# Hardwiring.net
KiCad netlist of a schematic drawn in Altium Designer
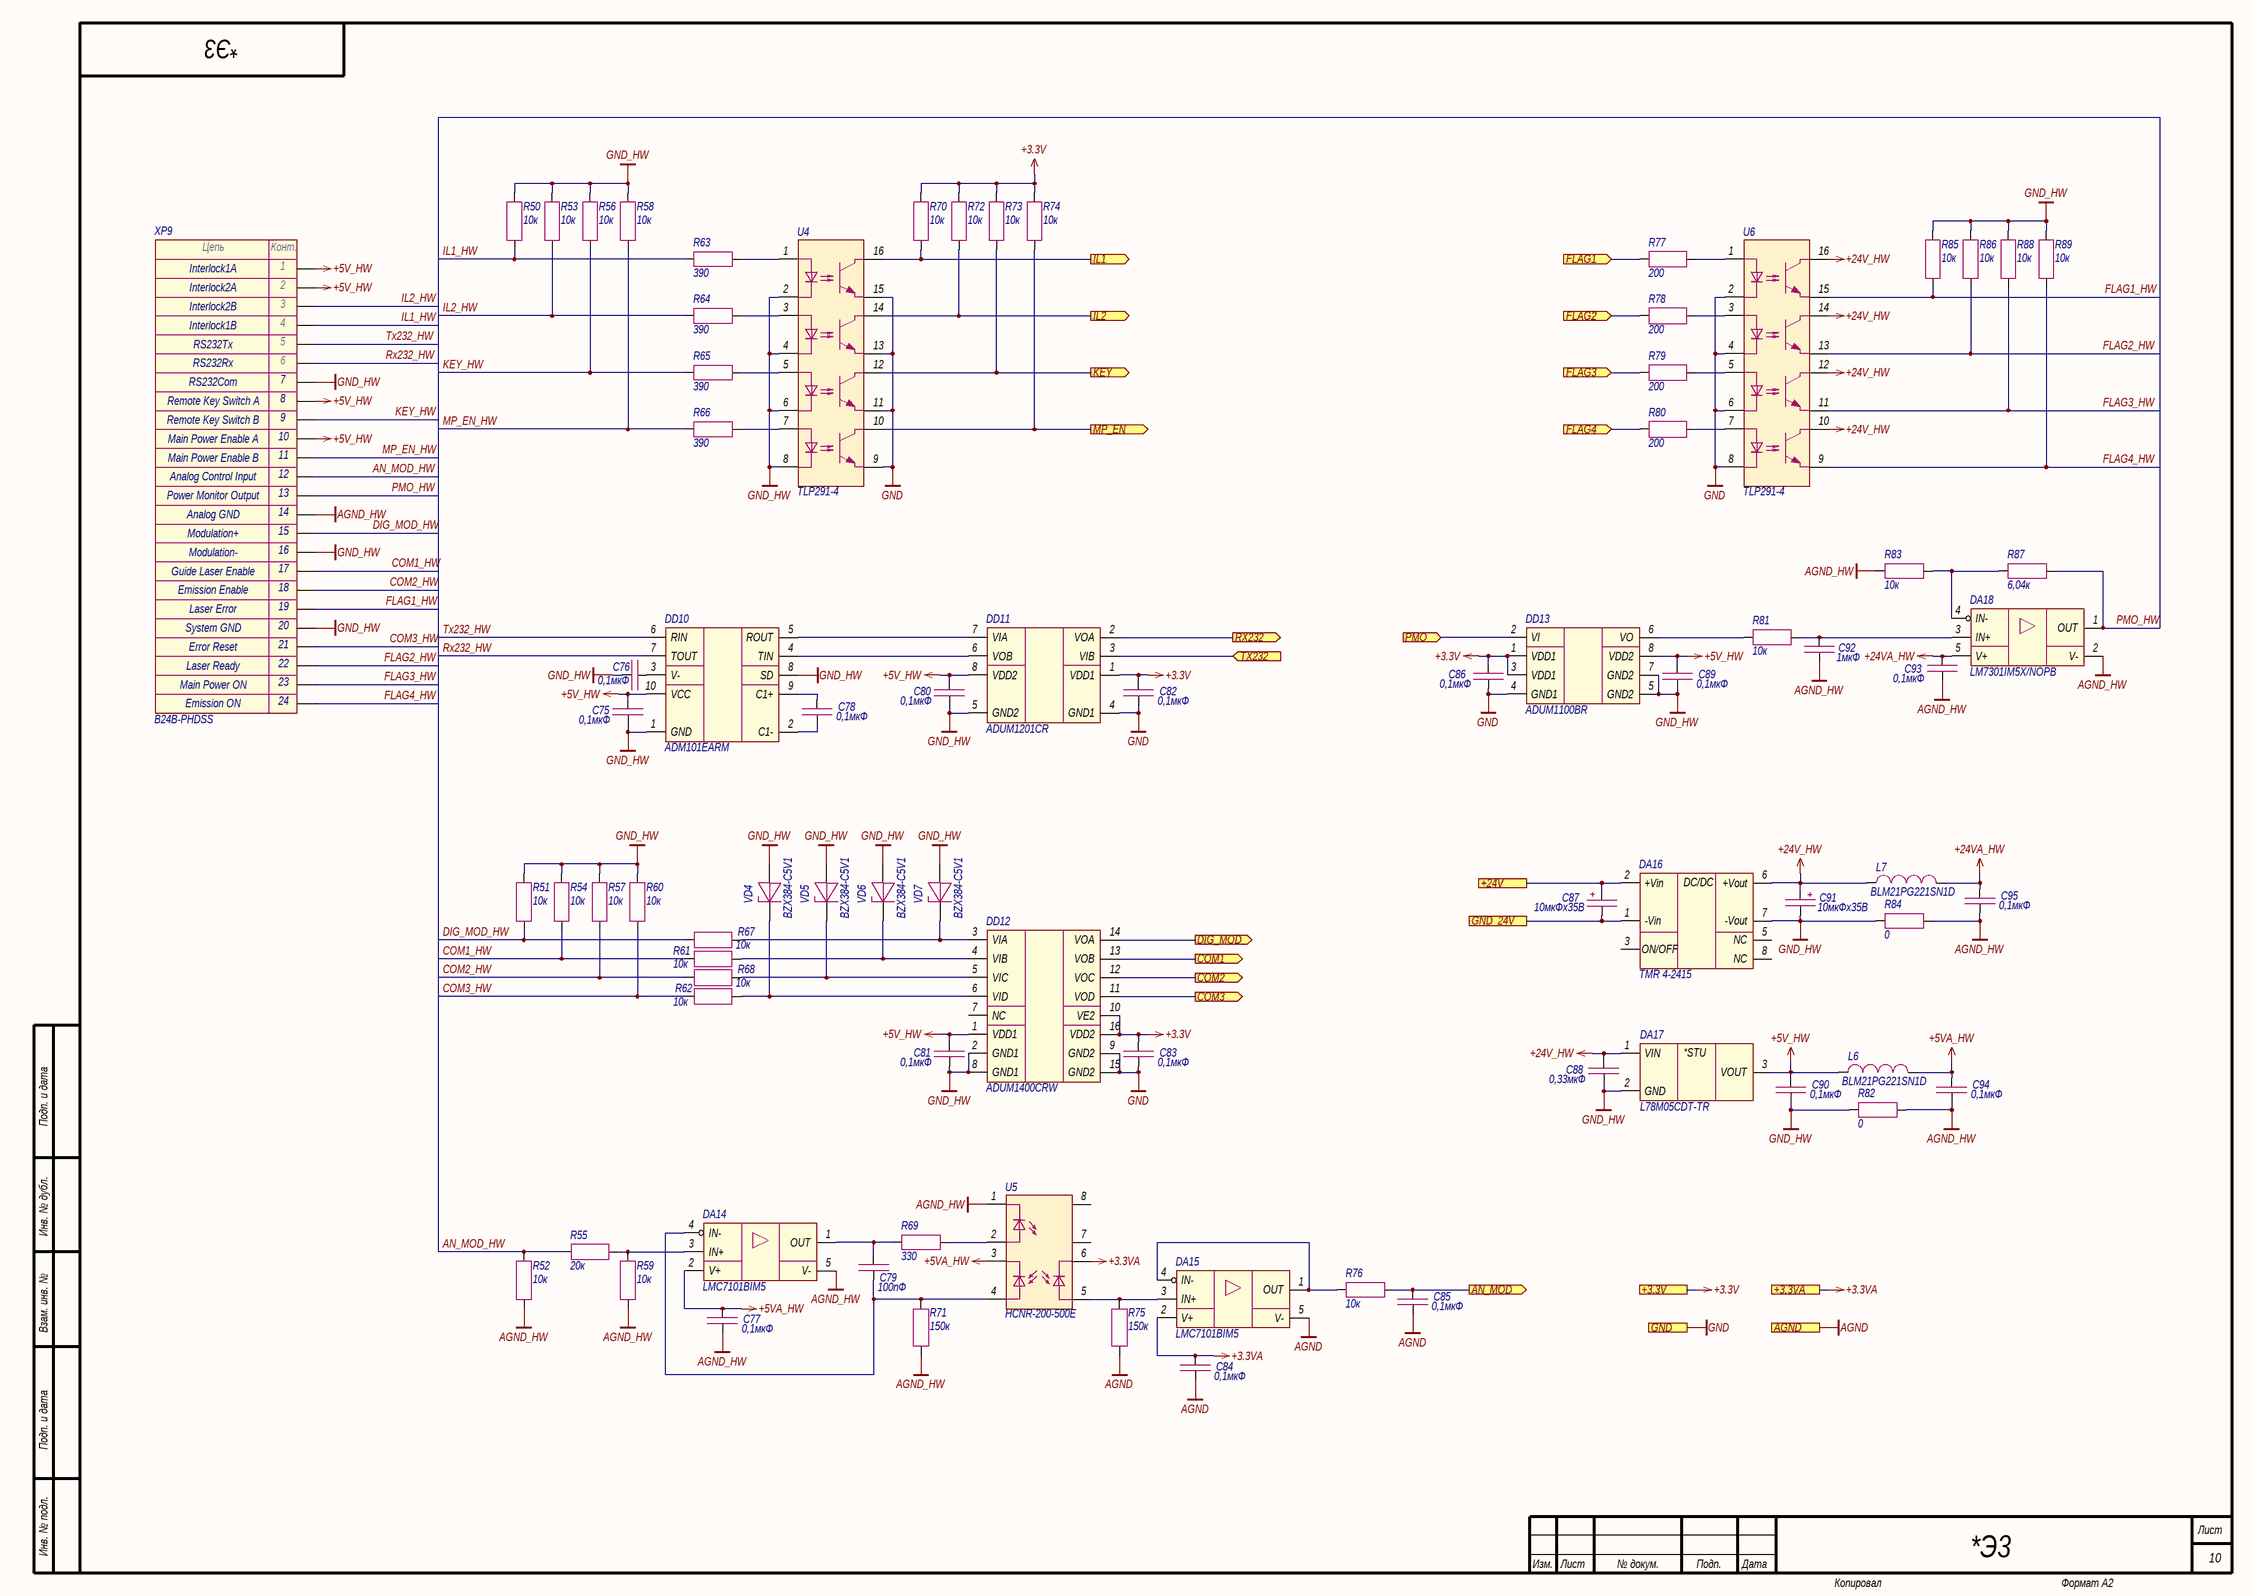
[diagram p0: Hardwiring.SchDoc]

(export (version "E")
  (design (tool "Eeschema 10.0.6"))
  (components
    (comp (ref "C75")
      (value "0,1мкФ")
      (footprint "Pcb_library:CAP_0603")
      (fields (field (name "MANUFACTURER") "Murata"))
      (libsource (lib "Schem_library") (part "Capacitor"))
    )
    (comp (ref "C76")
      (value "0,1мкФ")
      (footprint "Pcb_library:CAP_0603")
      (fields (field (name "MANUFACTURER") "Murata"))
      (libsource (lib "Schem_library") (part "Capacitor"))
    )
    (comp (ref "C77")
      (value "0,1мкФ")
      (footprint "Pcb_library:CAP_0603")
      (fields (field (name "MANUFACTURER") "Murata"))
      (libsource (lib "Schem_library") (part "Capacitor"))
    )
    (comp (ref "C78")
      (value "0,1мкФ")
      (footprint "Pcb_library:CAP_0603")
      (fields (field (name "MANUFACTURER") "Murata"))
      (libsource (lib "Schem_library") (part "Capacitor"))
    )
    (comp (ref "C79")
      (value "100пФ")
      (footprint "Pcb_library:CAP_0603")
      (fields (field (name "MANUFACTURER") "Murata"))
      (libsource (lib "Schem_library") (part "Capacitor"))
    )
    (comp (ref "C80")
      (value "0,1мкФ")
      (footprint "Pcb_library:CAP_0603")
      (fields (field (name "MANUFACTURER") "Murata"))
      (libsource (lib "Schem_library") (part "Capacitor"))
    )
    (comp (ref "C81")
      (value "0,1мкФ")
      (footprint "Pcb_library:CAP_0603")
      (fields (field (name "MANUFACTURER") "Murata"))
      (libsource (lib "Schem_library") (part "Capacitor"))
    )
    (comp (ref "C82")
      (value "0,1мкФ")
      (footprint "Pcb_library:CAP_0603")
      (fields (field (name "MANUFACTURER") "Murata"))
      (libsource (lib "Schem_library") (part "Capacitor"))
    )
    (comp (ref "C83")
      (value "0,1мкФ")
      (footprint "Pcb_library:CAP_0603")
      (fields (field (name "MANUFACTURER") "Murata"))
      (libsource (lib "Schem_library") (part "Capacitor"))
    )
    (comp (ref "C84")
      (value "0,1мкФ")
      (footprint "Pcb_library:CAP_0603")
      (fields (field (name "MANUFACTURER") "Murata"))
      (libsource (lib "Schem_library") (part "Capacitor"))
    )
    (comp (ref "C85")
      (value "0,1мкФ")
      (footprint "Pcb_library:CAP_0603")
      (fields (field (name "MANUFACTURER") "Murata"))
      (libsource (lib "Schem_library") (part "Capacitor"))
    )
    (comp (ref "C86")
      (value "0,1мкФ")
      (footprint "Pcb_library:CAP_0603")
      (fields (field (name "MANUFACTURER") "Murata"))
      (libsource (lib "Schem_library") (part "Capacitor"))
    )
    (comp (ref "C87")
      (value "10мкФх35B")
      (footprint "Pcb_library:CAP_C")
      (libsource (lib "Schem_library") (part "Capacitor_Polar"))
    )
    (comp (ref "C88")
      (value "0,33мкФ")
      (footprint "Pcb_library:CAP_0805")
      (fields (field (name "MANUFACTURER") "Murata"))
      (libsource (lib "Schem_library") (part "Capacitor"))
    )
    (comp (ref "C89")
      (value "0,1мкФ")
      (footprint "Pcb_library:CAP_0603")
      (fields (field (name "MANUFACTURER") "Murata"))
      (libsource (lib "Schem_library") (part "Capacitor"))
    )
    (comp (ref "C90")
      (value "0,1мкФ")
      (footprint "Pcb_library:CAP_0603")
      (fields (field (name "MANUFACTURER") "Murata"))
      (libsource (lib "Schem_library") (part "Capacitor"))
    )
    (comp (ref "C91")
      (value "10мкФх35B")
      (footprint "Pcb_library:CAP_C")
      (libsource (lib "Schem_library") (part "Capacitor_Polar"))
    )
    (comp (ref "C92")
      (value "1мкФ")
      (footprint "Pcb_library:CAP_0603")
      (fields (field (name "MANUFACTURER") "Murata"))
      (libsource (lib "Schem_library") (part "Capacitor"))
    )
    (comp (ref "C93")
      (value "0,1мкФ")
      (footprint "Pcb_library:CAP_0603")
      (fields (field (name "MANUFACTURER") "Murata"))
      (libsource (lib "Schem_library") (part "Capacitor"))
    )
    (comp (ref "C94")
      (value "0,1мкФ")
      (footprint "Pcb_library:CAP_0603")
      (fields (field (name "MANUFACTURER") "Murata"))
      (libsource (lib "Schem_library") (part "Capacitor"))
    )
    (comp (ref "C95")
      (value "0,1мкФ")
      (footprint "Pcb_library:CAP_0603")
      (fields (field (name "MANUFACTURER") "Murata"))
      (libsource (lib "Schem_library") (part "Capacitor"))
    )
    (comp (ref "DA14")
      (value "LMC7101BIM5")
      (footprint "Pcb_library:SOT-23-5")
      (fields (field (name "MANUFACTURER") "Texas Instruments"))
      (libsource (lib "Schem_library") (part "LMC7101"))
    )
    (comp (ref "DA15")
      (value "LMC7101BIM5")
      (footprint "Pcb_library:SOT-23-5")
      (fields (field (name "MANUFACTURER") "Texas Instruments"))
      (libsource (lib "Schem_library") (part "LMC7101"))
    )
    (comp (ref "DA16")
      (value "TMR 4-2415")
      (footprint "Pcb_library:TMR4 (SIP-8)")
      (fields (field (name "MANUFACTURER") "Traco Power"))
      (libsource (lib "Schem_library") (part "TMR4"))
    )
    (comp (ref "DA17")
      (value "L78M05CDT-TR")
      (footprint "Pcb_library:TO-252")
      (fields (field (name "MANUFACTURER") "STMicroelectronics"))
      (libsource (lib "Schem_library") (part "L78M"))
    )
    (comp (ref "DA18")
      (value "LM7301IM5X/NOPB")
      (footprint "Pcb_library:SOT-23-5")
      (fields (field (name "MANUFACTURER") "Texas Instruments"))
      (libsource (lib "Schem_library") (part "LM7301IM5"))
    )
    (comp (ref "DD10")
      (value "ADM101EARM")
      (footprint "Pcb_library:MSOP-10")
      (fields (field (name "MANUFACTURER") "Analog Devices"))
      (libsource (lib "Schem_library") (part "ADM101EARM"))
    )
    (comp (ref "DD11")
      (value "ADUM1201CR")
      (footprint "Pcb_library:SOIC-8")
      (fields (field (name "MANUFACTURER") "Analog Devices"))
      (libsource (lib "Schem_library") (part "ADUM1201"))
    )
    (comp (ref "DD12")
      (value "ADUM1400CRW")
      (footprint "Pcb_library:SOIC-16W")
      (fields (field (name "MANUFACTURER") "Analog Devices"))
      (libsource (lib "Schem_library") (part "ADUM1400"))
    )
    (comp (ref "DD13")
      (value "ADUM1100BR")
      (footprint "Pcb_library:SOIC-8")
      (fields (field (name "MANUFACTURER") "Analog Devices"))
      (libsource (lib "Schem_library") (part "ADUM1100"))
    )
    (comp (ref "L6")
      (value "BLM21PG221SN1D")
      (footprint "Pcb_library:IND_0805")
      (fields (field (name "MANUFACTURER") "Murata"))
      (libsource (lib "Schem_library") (part "Inductor"))
    )
    (comp (ref "L7")
      (value "BLM21PG221SN1D")
      (footprint "Pcb_library:IND_0805")
      (fields (field (name "MANUFACTURER") "Murata"))
      (libsource (lib "Schem_library") (part "Inductor"))
    )
    (comp (ref "R50")
      (value "10к")
      (footprint "Pcb_library:RES_0603")
      (fields (field (name "MANUFACTURER") "Yageo"))
      (libsource (lib "Schem_library") (part "Resistor"))
    )
    (comp (ref "R51")
      (value "10к")
      (footprint "Pcb_library:RES_0603")
      (fields (field (name "MANUFACTURER") "Yageo"))
      (libsource (lib "Schem_library") (part "Resistor"))
    )
    (comp (ref "R52")
      (value "10к")
      (footprint "Pcb_library:RES_0603")
      (fields (field (name "MANUFACTURER") "Yageo"))
      (libsource (lib "Schem_library") (part "Resistor"))
    )
    (comp (ref "R53")
      (value "10к")
      (footprint "Pcb_library:RES_0603")
      (fields (field (name "MANUFACTURER") "Yageo"))
      (libsource (lib "Schem_library") (part "Resistor"))
    )
    (comp (ref "R54")
      (value "10к")
      (footprint "Pcb_library:RES_0603")
      (fields (field (name "MANUFACTURER") "Yageo"))
      (libsource (lib "Schem_library") (part "Resistor"))
    )
    (comp (ref "R55")
      (value "20к")
      (footprint "Pcb_library:RES_0603")
      (fields (field (name "MANUFACTURER") "Yageo"))
      (libsource (lib "Schem_library") (part "Resistor"))
    )
    (comp (ref "R56")
      (value "10к")
      (footprint "Pcb_library:RES_0603")
      (fields (field (name "MANUFACTURER") "Yageo"))
      (libsource (lib "Schem_library") (part "Resistor"))
    )
    (comp (ref "R57")
      (value "10к")
      (footprint "Pcb_library:RES_0603")
      (fields (field (name "MANUFACTURER") "Yageo"))
      (libsource (lib "Schem_library") (part "Resistor"))
    )
    (comp (ref "R58")
      (value "10к")
      (footprint "Pcb_library:RES_0603")
      (fields (field (name "MANUFACTURER") "Yageo"))
      (libsource (lib "Schem_library") (part "Resistor"))
    )
    (comp (ref "R59")
      (value "10к")
      (footprint "Pcb_library:RES_0603")
      (fields (field (name "MANUFACTURER") "Yageo"))
      (libsource (lib "Schem_library") (part "Resistor"))
    )
    (comp (ref "R60")
      (value "10к")
      (footprint "Pcb_library:RES_0603")
      (fields (field (name "MANUFACTURER") "Yageo"))
      (libsource (lib "Schem_library") (part "Resistor"))
    )
    (comp (ref "R61")
      (value "10к")
      (footprint "Pcb_library:RES_0603")
      (fields (field (name "MANUFACTURER") "Yageo"))
      (libsource (lib "Schem_library") (part "Resistor"))
    )
    (comp (ref "R62")
      (value "10к")
      (footprint "Pcb_library:RES_0603")
      (fields (field (name "MANUFACTURER") "Yageo"))
      (libsource (lib "Schem_library") (part "Resistor"))
    )
    (comp (ref "R63")
      (value "390")
      (footprint "Pcb_library:RES_0603")
      (fields (field (name "MANUFACTURER") "Yageo"))
      (libsource (lib "Schem_library") (part "Resistor"))
    )
    (comp (ref "R64")
      (value "390")
      (footprint "Pcb_library:RES_0603")
      (fields (field (name "MANUFACTURER") "Yageo"))
      (libsource (lib "Schem_library") (part "Resistor"))
    )
    (comp (ref "R65")
      (value "390")
      (footprint "Pcb_library:RES_0603")
      (fields (field (name "MANUFACTURER") "Yageo"))
      (libsource (lib "Schem_library") (part "Resistor"))
    )
    (comp (ref "R66")
      (value "390")
      (footprint "Pcb_library:RES_0603")
      (fields (field (name "MANUFACTURER") "Yageo"))
      (libsource (lib "Schem_library") (part "Resistor"))
    )
    (comp (ref "R67")
      (value "10к")
      (footprint "Pcb_library:RES_0603")
      (fields (field (name "MANUFACTURER") "Yageo"))
      (libsource (lib "Schem_library") (part "Resistor"))
    )
    (comp (ref "R68")
      (value "10к")
      (footprint "Pcb_library:RES_0603")
      (fields (field (name "MANUFACTURER") "Yageo"))
      (libsource (lib "Schem_library") (part "Resistor"))
    )
    (comp (ref "R69")
      (value "330")
      (footprint "Pcb_library:RES_0603")
      (fields (field (name "MANUFACTURER") "Yageo"))
      (libsource (lib "Schem_library") (part "Resistor"))
    )
    (comp (ref "R70")
      (value "10к")
      (footprint "Pcb_library:RES_0603")
      (fields (field (name "MANUFACTURER") "Yageo"))
      (libsource (lib "Schem_library") (part "Resistor"))
    )
    (comp (ref "R71")
      (value "150к")
      (footprint "Pcb_library:RES_0603")
      (fields (field (name "MANUFACTURER") "Yageo"))
      (libsource (lib "Schem_library") (part "Resistor"))
    )
    (comp (ref "R72")
      (value "10к")
      (footprint "Pcb_library:RES_0603")
      (fields (field (name "MANUFACTURER") "Yageo"))
      (libsource (lib "Schem_library") (part "Resistor"))
    )
    (comp (ref "R73")
      (value "10к")
      (footprint "Pcb_library:RES_0603")
      (fields (field (name "MANUFACTURER") "Yageo"))
      (libsource (lib "Schem_library") (part "Resistor"))
    )
    (comp (ref "R74")
      (value "10к")
      (footprint "Pcb_library:RES_0603")
      (fields (field (name "MANUFACTURER") "Yageo"))
      (libsource (lib "Schem_library") (part "Resistor"))
    )
    (comp (ref "R75")
      (value "150к")
      (footprint "Pcb_library:RES_0603")
      (fields (field (name "MANUFACTURER") "Yageo"))
      (libsource (lib "Schem_library") (part "Resistor"))
    )
    (comp (ref "R76")
      (value "10к")
      (footprint "Pcb_library:RES_0603")
      (fields (field (name "MANUFACTURER") "Yageo"))
      (libsource (lib "Schem_library") (part "Resistor"))
    )
    (comp (ref "R77")
      (value "200")
      (footprint "Pcb_library:RES_0603")
      (fields (field (name "MANUFACTURER") "Yageo"))
      (libsource (lib "Schem_library") (part "Resistor"))
    )
    (comp (ref "R78")
      (value "200")
      (footprint "Pcb_library:RES_0603")
      (fields (field (name "MANUFACTURER") "Yageo"))
      (libsource (lib "Schem_library") (part "Resistor"))
    )
    (comp (ref "R79")
      (value "200")
      (footprint "Pcb_library:RES_0603")
      (fields (field (name "MANUFACTURER") "Yageo"))
      (libsource (lib "Schem_library") (part "Resistor"))
    )
    (comp (ref "R80")
      (value "200")
      (footprint "Pcb_library:RES_0603")
      (fields (field (name "MANUFACTURER") "Yageo"))
      (libsource (lib "Schem_library") (part "Resistor"))
    )
    (comp (ref "R81")
      (value "10к")
      (footprint "Pcb_library:RES_0603")
      (fields (field (name "MANUFACTURER") "Yageo"))
      (libsource (lib "Schem_library") (part "Resistor"))
    )
    (comp (ref "R82")
      (value "0")
      (footprint "Pcb_library:RES_0805")
      (fields (field (name "MANUFACTURER") "Yageo"))
      (libsource (lib "Schem_library") (part "Resistor"))
    )
    (comp (ref "R83")
      (value "10к")
      (footprint "Pcb_library:RES_0603")
      (fields (field (name "MANUFACTURER") "Yageo"))
      (libsource (lib "Schem_library") (part "Resistor"))
    )
    (comp (ref "R84")
      (value "0")
      (footprint "Pcb_library:RES_0805")
      (fields (field (name "MANUFACTURER") "Yageo"))
      (libsource (lib "Schem_library") (part "Resistor"))
    )
    (comp (ref "R85")
      (value "10к")
      (footprint "Pcb_library:RES_0603")
      (fields (field (name "MANUFACTURER") "Yageo"))
      (libsource (lib "Schem_library") (part "Resistor"))
    )
    (comp (ref "R86")
      (value "10к")
      (footprint "Pcb_library:RES_0603")
      (fields (field (name "MANUFACTURER") "Yageo"))
      (libsource (lib "Schem_library") (part "Resistor"))
    )
    (comp (ref "R87")
      (value "6,04к")
      (footprint "Pcb_library:RES_0603")
      (fields (field (name "MANUFACTURER") "Yageo"))
      (libsource (lib "Schem_library") (part "Resistor"))
    )
    (comp (ref "R88")
      (value "10к")
      (footprint "Pcb_library:RES_0603")
      (fields (field (name "MANUFACTURER") "Yageo"))
      (libsource (lib "Schem_library") (part "Resistor"))
    )
    (comp (ref "R89")
      (value "10к")
      (footprint "Pcb_library:RES_0603")
      (fields (field (name "MANUFACTURER") "Yageo"))
      (libsource (lib "Schem_library") (part "Resistor"))
    )
    (comp (ref "U4")
      (value "TLP291-4")
      (footprint "Pcb_library:SOP-16")
      (fields (field (name "MANUFACTURER") "Toshiba"))
      (libsource (lib "Schem_library") (part "TLP281-4"))
    )
    (comp (ref "U5")
      (value "HCNR-200-500E")
      (footprint "Pcb_library:HCNR200")
      (fields (field (name "MANUFACTURER") "Avago"))
      (libsource (lib "Schem_library") (part "HCNR200"))
    )
    (comp (ref "U6")
      (value "TLP291-4")
      (footprint "Pcb_library:SOP-16")
      (fields (field (name "MANUFACTURER") "Toshiba"))
      (libsource (lib "Schem_library") (part "TLP281-4"))
    )
    (comp (ref "VD4")
      (value "BZX384-C5V1")
      (footprint "Pcb_library:SOD-323")
      (fields (field (name "MANUFACTURER") "Nexperia"))
      (libsource (lib "Schem_library") (part "Diode_Zener"))
    )
    (comp (ref "VD5")
      (value "BZX384-C5V1")
      (footprint "Pcb_library:SOD-323")
      (fields (field (name "MANUFACTURER") "Nexperia"))
      (libsource (lib "Schem_library") (part "Diode_Zener"))
    )
    (comp (ref "VD6")
      (value "BZX384-C5V1")
      (footprint "Pcb_library:SOD-323")
      (fields (field (name "MANUFACTURER") "Nexperia"))
      (libsource (lib "Schem_library") (part "Diode_Zener"))
    )
    (comp (ref "VD7")
      (value "BZX384-C5V1")
      (footprint "Pcb_library:SOD-323")
      (fields (field (name "MANUFACTURER") "Nexperia"))
      (libsource (lib "Schem_library") (part "Diode_Zener"))
    )
    (comp (ref "XP9")
      (value "B24B-PHDSS")
      (footprint "Pcb_library:B24B-PHDSS")
      (fields (field (name "MANUFACTURER") "JST"))
      (libsource (lib "Schem_library") (part "Connector-24"))
    )
  )
  (nets
    (net (code "1") (name "+3.3V") (class "Default")
      (node (ref "C82") (pin "1") (pinfunction "1_1") (pintype "passive"))
      (node (ref "C83") (pin "1") (pinfunction "1_1") (pintype "passive"))
      (node (ref "C86") (pin "1") (pinfunction "1_1") (pintype "passive"))
      (node (ref "DD11") (pin "1") (pinfunction "VDD1_1") (pintype "passive"))
      (node (ref "DD12") (pin "10") (pinfunction "VE2_10") (pintype "passive"))
      (node (ref "DD12") (pin "16") (pinfunction "VDD2_16") (pintype "passive"))
      (node (ref "DD13") (pin "1") (pinfunction "VDD1_1") (pintype "passive"))
      (node (ref "DD13") (pin "3") (pinfunction "VDD1_3") (pintype "passive"))
      (node (ref "R70") (pin "1") (pinfunction "1_1") (pintype "passive"))
      (node (ref "R72") (pin "1") (pinfunction "1_1") (pintype "passive"))
      (node (ref "R73") (pin "1") (pinfunction "1_1") (pintype "passive"))
      (node (ref "R74") (pin "1") (pinfunction "1_1") (pintype "passive"))
    )
    (net (code "2") (name "+3.3VA") (class "Default")
      (node (ref "C84") (pin "1") (pinfunction "1_1") (pintype "passive"))
      (node (ref "DA15") (pin "2") (pinfunction "V+_2") (pintype "passive"))
      (node (ref "U5") (pin "6") (pintype "passive"))
    )
    (net (code "3") (name "+5VA_HW") (class "Default")
      (node (ref "C77") (pin "1") (pinfunction "1_1") (pintype "passive"))
      (node (ref "C94") (pin "1") (pinfunction "1_1") (pintype "passive"))
      (node (ref "DA14") (pin "2") (pinfunction "V+_2") (pintype "passive"))
      (node (ref "L6") (pin "2") (pinfunction "2_2") (pintype "passive"))
      (node (ref "U5") (pin "3") (pintype "passive"))
    )
    (net (code "4") (name "+5V_HW") (class "Default")
      (node (ref "C75") (pin "1") (pinfunction "1_1") (pintype "passive"))
      (node (ref "C80") (pin "1") (pinfunction "1_1") (pintype "passive"))
      (node (ref "C81") (pin "1") (pinfunction "1_1") (pintype "passive"))
      (node (ref "C89") (pin "1") (pinfunction "1_1") (pintype "passive"))
      (node (ref "C90") (pin "1") (pinfunction "1_1") (pintype "passive"))
      (node (ref "DA17") (pin "3") (pinfunction "VOUT_3") (pintype "passive"))
      (node (ref "DD10") (pin "10") (pinfunction "VCC_10") (pintype "passive"))
      (node (ref "DD11") (pin "8") (pinfunction "VDD2_8") (pintype "passive"))
      (node (ref "DD12") (pin "1") (pinfunction "VDD1_1") (pintype "passive"))
      (node (ref "DD13") (pin "8") (pinfunction "VDD2_8") (pintype "passive"))
      (node (ref "L6") (pin "1") (pinfunction "1_1") (pintype "passive"))
      (node (ref "XP9") (pin "1") (pintype "passive"))
      (node (ref "XP9") (pin "10") (pintype "passive"))
      (node (ref "XP9") (pin "2") (pintype "passive"))
      (node (ref "XP9") (pin "8") (pintype "passive"))
    )
    (net (code "5") (name "+24VA_HW") (class "Default")
      (node (ref "C93") (pin "1") (pinfunction "1_1") (pintype "passive"))
      (node (ref "C95") (pin "1") (pinfunction "1_1") (pintype "passive"))
      (node (ref "DA18") (pin "5") (pinfunction "V+_5") (pintype "passive"))
      (node (ref "L7") (pin "2") (pinfunction "2_2") (pintype "passive"))
    )
    (net (code "6") (name "+24V_HW") (class "Default")
      (node (ref "C88") (pin "2") (pinfunction "2_2") (pintype "passive"))
      (node (ref "C91") (pin "1") (pinfunction "1_1") (pintype "passive"))
      (node (ref "DA16") (pin "6") (pinfunction "+Vout_6") (pintype "passive"))
      (node (ref "DA17") (pin "1") (pinfunction "VIN_1") (pintype "passive"))
      (node (ref "L7") (pin "1") (pinfunction "1_1") (pintype "passive"))
      (node (ref "U6") (pin "10") (pintype "passive"))
      (node (ref "U6") (pin "12") (pintype "passive"))
      (node (ref "U6") (pin "14") (pintype "passive"))
      (node (ref "U6") (pin "16") (pintype "passive"))
    )
    (net (code "7") (name "/+24V") (class "Default")
      (node (ref "C87") (pin "1") (pinfunction "1_1") (pintype "passive"))
      (node (ref "DA16") (pin "2") (pinfunction "+Vin_2") (pintype "passive"))
    )
    (net (code "8") (name "/AN_MOD") (class "Default")
      (node (ref "C85") (pin "1") (pinfunction "1_1") (pintype "passive"))
      (node (ref "R76") (pin "2") (pinfunction "2_2") (pintype "passive"))
    )
    (net (code "9") (name "/AN_MOD_HW") (class "Default")
      (node (ref "R52") (pin "1") (pinfunction "1_1") (pintype "passive"))
      (node (ref "R55") (pin "1") (pinfunction "1_1") (pintype "passive"))
      (node (ref "XP9") (pin "12") (pintype "passive"))
    )
    (net (code "10") (name "/COM1") (class "Default")
      (node (ref "DD12") (pin "13") (pinfunction "VOB_13") (pintype "passive"))
    )
    (net (code "11") (name "/COM1_HW") (class "Default")
      (node (ref "R54") (pin "2") (pinfunction "2_2") (pintype "passive"))
      (node (ref "R61") (pin "1") (pinfunction "1_1") (pintype "passive"))
      (node (ref "XP9") (pin "17") (pintype "passive"))
    )
    (net (code "12") (name "/COM2") (class "Default")
      (node (ref "DD12") (pin "12") (pinfunction "VOC_12") (pintype "passive"))
    )
    (net (code "13") (name "/COM2_HW") (class "Default")
      (node (ref "R57") (pin "2") (pinfunction "2_2") (pintype "passive"))
      (node (ref "R68") (pin "1") (pinfunction "1_1") (pintype "passive"))
      (node (ref "XP9") (pin "18") (pintype "passive"))
    )
    (net (code "14") (name "/COM3") (class "Default")
      (node (ref "DD12") (pin "11") (pinfunction "VOD_11") (pintype "passive"))
    )
    (net (code "15") (name "/COM3_HW") (class "Default")
      (node (ref "R60") (pin "2") (pinfunction "2_2") (pintype "passive"))
      (node (ref "R62") (pin "1") (pinfunction "1_1") (pintype "passive"))
      (node (ref "XP9") (pin "21") (pintype "passive"))
    )
    (net (code "16") (name "/DIG_MOD") (class "Default")
      (node (ref "DD12") (pin "14") (pinfunction "VOA_14") (pintype "passive"))
    )
    (net (code "17") (name "/DIG_MOD_HW") (class "Default")
      (node (ref "R51") (pin "2") (pinfunction "2_2") (pintype "passive"))
      (node (ref "R67") (pin "1") (pinfunction "1_1") (pintype "passive"))
      (node (ref "XP9") (pin "15") (pintype "passive"))
    )
    (net (code "18") (name "/FLAG1") (class "Default")
      (node (ref "R77") (pin "2") (pinfunction "2_2") (pintype "passive"))
    )
    (net (code "19") (name "/FLAG1_HW") (class "Default")
      (node (ref "R85") (pin "2") (pinfunction "2_2") (pintype "passive"))
      (node (ref "U6") (pin "15") (pintype "passive"))
      (node (ref "XP9") (pin "19") (pintype "passive"))
    )
    (net (code "20") (name "/FLAG2") (class "Default")
      (node (ref "R78") (pin "2") (pinfunction "2_2") (pintype "passive"))
    )
    (net (code "21") (name "/FLAG2_HW") (class "Default")
      (node (ref "R86") (pin "2") (pinfunction "2_2") (pintype "passive"))
      (node (ref "U6") (pin "13") (pintype "passive"))
      (node (ref "XP9") (pin "22") (pintype "passive"))
    )
    (net (code "22") (name "/FLAG3") (class "Default")
      (node (ref "R79") (pin "2") (pinfunction "2_2") (pintype "passive"))
    )
    (net (code "23") (name "/FLAG3_HW") (class "Default")
      (node (ref "R88") (pin "2") (pinfunction "2_2") (pintype "passive"))
      (node (ref "U6") (pin "11") (pintype "passive"))
      (node (ref "XP9") (pin "23") (pintype "passive"))
    )
    (net (code "24") (name "/FLAG4") (class "Default")
      (node (ref "R80") (pin "2") (pinfunction "2_2") (pintype "passive"))
    )
    (net (code "25") (name "/FLAG4_HW") (class "Default")
      (node (ref "R89") (pin "2") (pinfunction "2_2") (pintype "passive"))
      (node (ref "U6") (pin "9") (pintype "passive"))
      (node (ref "XP9") (pin "24") (pintype "passive"))
    )
    (net (code "26") (name "/GND_24V") (class "Default")
      (node (ref "C87") (pin "2") (pinfunction "2_2") (pintype "passive"))
      (node (ref "DA16") (pin "1") (pinfunction "-Vin_1") (pintype "passive"))
    )
    (net (code "27") (name "/IL1") (class "Default")
      (node (ref "R70") (pin "2") (pinfunction "2_2") (pintype "passive"))
      (node (ref "U4") (pin "16") (pintype "passive"))
    )
    (net (code "28") (name "/IL1_HW") (class "Default")
      (node (ref "R50") (pin "2") (pinfunction "2_2") (pintype "passive"))
      (node (ref "R63") (pin "1") (pinfunction "1_1") (pintype "passive"))
      (node (ref "XP9") (pin "4") (pintype "passive"))
    )
    (net (code "29") (name "/IL2") (class "Default")
      (node (ref "R72") (pin "2") (pinfunction "2_2") (pintype "passive"))
      (node (ref "U4") (pin "14") (pintype "passive"))
    )
    (net (code "30") (name "/IL2_HW") (class "Default")
      (node (ref "R53") (pin "2") (pinfunction "2_2") (pintype "passive"))
      (node (ref "R64") (pin "1") (pinfunction "1_1") (pintype "passive"))
      (node (ref "XP9") (pin "3") (pintype "passive"))
    )
    (net (code "31") (name "/KEY") (class "Default")
      (node (ref "R73") (pin "2") (pinfunction "2_2") (pintype "passive"))
      (node (ref "U4") (pin "12") (pintype "passive"))
    )
    (net (code "32") (name "/KEY_HW") (class "Default")
      (node (ref "R56") (pin "2") (pinfunction "2_2") (pintype "passive"))
      (node (ref "R65") (pin "1") (pinfunction "1_1") (pintype "passive"))
      (node (ref "XP9") (pin "9") (pintype "passive"))
    )
    (net (code "33") (name "/MP_EN") (class "Default")
      (node (ref "R74") (pin "2") (pinfunction "2_2") (pintype "passive"))
      (node (ref "U4") (pin "10") (pintype "passive"))
    )
    (net (code "34") (name "/MP_EN_HW") (class "Default")
      (node (ref "R58") (pin "2") (pinfunction "2_2") (pintype "passive"))
      (node (ref "R66") (pin "1") (pinfunction "1_1") (pintype "passive"))
      (node (ref "XP9") (pin "11") (pintype "passive"))
    )
    (net (code "35") (name "/PMO") (class "Default")
      (node (ref "DD13") (pin "2") (pinfunction "VI_2") (pintype "passive"))
    )
    (net (code "36") (name "/PMO_HW") (class "Default")
      (node (ref "DA18") (pin "1") (pinfunction "OUT_1") (pintype "passive"))
      (node (ref "R87") (pin "2") (pinfunction "2_2") (pintype "passive"))
      (node (ref "XP9") (pin "13") (pintype "passive"))
    )
    (net (code "37") (name "/RX232") (class "Default")
      (node (ref "DD11") (pin "2") (pinfunction "VOA_2") (pintype "passive"))
    )
    (net (code "38") (name "/Rx232_HW") (class "Default")
      (node (ref "DD10") (pin "7") (pinfunction "TOUT_7") (pintype "passive"))
      (node (ref "XP9") (pin "6") (pintype "passive"))
    )
    (net (code "39") (name "/TX232") (class "Default")
      (node (ref "DD11") (pin "3") (pinfunction "VIB_3") (pintype "passive"))
    )
    (net (code "40") (name "/Tx232_HW") (class "Default")
      (node (ref "DD10") (pin "6") (pinfunction "RIN_6") (pintype "passive"))
      (node (ref "XP9") (pin "5") (pintype "passive"))
    )
    (net (code "41") (name "AGND") (class "Default")
      (node (ref "C84") (pin "2") (pinfunction "2_2") (pintype "passive"))
      (node (ref "C85") (pin "2") (pinfunction "2_2") (pintype "passive"))
      (node (ref "DA15") (pin "5") (pinfunction "V-_5") (pintype "passive"))
      (node (ref "R75") (pin "2") (pinfunction "2_2") (pintype "passive"))
    )
    (net (code "42") (name "AGND_HW") (class "Default")
      (node (ref "C77") (pin "2") (pinfunction "2_2") (pintype "passive"))
      (node (ref "C92") (pin "2") (pinfunction "2_2") (pintype "passive"))
      (node (ref "C93") (pin "2") (pinfunction "2_2") (pintype "passive"))
      (node (ref "C94") (pin "2") (pinfunction "2_2") (pintype "passive"))
      (node (ref "C95") (pin "2") (pinfunction "2_2") (pintype "passive"))
      (node (ref "DA14") (pin "5") (pinfunction "V-_5") (pintype "passive"))
      (node (ref "DA18") (pin "2") (pinfunction "V-_2") (pintype "passive"))
      (node (ref "R52") (pin "2") (pinfunction "2_2") (pintype "passive"))
      (node (ref "R59") (pin "2") (pinfunction "2_2") (pintype "passive"))
      (node (ref "R71") (pin "2") (pinfunction "2_2") (pintype "passive"))
      (node (ref "R82") (pin "2") (pinfunction "2_2") (pintype "passive"))
      (node (ref "R83") (pin "1") (pinfunction "1_1") (pintype "passive"))
      (node (ref "R84") (pin "2") (pinfunction "2_2") (pintype "passive"))
      (node (ref "U5") (pin "1") (pintype "passive"))
      (node (ref "XP9") (pin "14") (pintype "passive"))
    )
    (net (code "43") (name "GND") (class "Default")
      (node (ref "C82") (pin "2") (pinfunction "2_2") (pintype "passive"))
      (node (ref "C83") (pin "2") (pinfunction "2_2") (pintype "passive"))
      (node (ref "C86") (pin "2") (pinfunction "2_2") (pintype "passive"))
      (node (ref "DD11") (pin "4") (pinfunction "GND1_4") (pintype "passive"))
      (node (ref "DD12") (pin "15") (pinfunction "GND2_15") (pintype "passive"))
      (node (ref "DD12") (pin "9") (pinfunction "GND2_9") (pintype "passive"))
      (node (ref "DD13") (pin "4") (pinfunction "GND1_4") (pintype "passive"))
      (node (ref "U4") (pin "11") (pintype "passive"))
      (node (ref "U4") (pin "13") (pintype "passive"))
      (node (ref "U4") (pin "15") (pintype "passive"))
      (node (ref "U4") (pin "9") (pintype "passive"))
      (node (ref "U6") (pin "2") (pintype "passive"))
      (node (ref "U6") (pin "4") (pintype "passive"))
      (node (ref "U6") (pin "6") (pintype "passive"))
      (node (ref "U6") (pin "8") (pintype "passive"))
    )
    (net (code "44") (name "GND_HW") (class "Default")
      (node (ref "C75") (pin "2") (pinfunction "2_2") (pintype "passive"))
      (node (ref "C76") (pin "2") (pinfunction "2_2") (pintype "passive"))
      (node (ref "C80") (pin "2") (pinfunction "2_2") (pintype "passive"))
      (node (ref "C81") (pin "2") (pinfunction "2_2") (pintype "passive"))
      (node (ref "C88") (pin "1") (pinfunction "1_1") (pintype "passive"))
      (node (ref "C89") (pin "2") (pinfunction "2_2") (pintype "passive"))
      (node (ref "C90") (pin "2") (pinfunction "2_2") (pintype "passive"))
      (node (ref "C91") (pin "2") (pinfunction "2_2") (pintype "passive"))
      (node (ref "DA16") (pin "7") (pinfunction "-Vout_7") (pintype "passive"))
      (node (ref "DA17") (pin "2") (pinfunction "GND_2") (pintype "passive"))
      (node (ref "DD10") (pin "1") (pinfunction "GND_1") (pintype "passive"))
      (node (ref "DD10") (pin "8") (pinfunction "SD_8") (pintype "passive"))
      (node (ref "DD11") (pin "5") (pinfunction "GND2_5") (pintype "passive"))
      (node (ref "DD12") (pin "2") (pinfunction "GND1_2") (pintype "passive"))
      (node (ref "DD12") (pin "8") (pinfunction "GND1_8") (pintype "passive"))
      (node (ref "DD13") (pin "5") (pinfunction "GND2_5") (pintype "passive"))
      (node (ref "DD13") (pin "7") (pinfunction "GND2_7") (pintype "passive"))
      (node (ref "R50") (pin "1") (pinfunction "1_1") (pintype "passive"))
      (node (ref "R51") (pin "1") (pinfunction "1_1") (pintype "passive"))
      (node (ref "R53") (pin "1") (pinfunction "1_1") (pintype "passive"))
      (node (ref "R54") (pin "1") (pinfunction "1_1") (pintype "passive"))
      (node (ref "R56") (pin "1") (pinfunction "1_1") (pintype "passive"))
      (node (ref "R57") (pin "1") (pinfunction "1_1") (pintype "passive"))
      (node (ref "R58") (pin "1") (pinfunction "1_1") (pintype "passive"))
      (node (ref "R60") (pin "1") (pinfunction "1_1") (pintype "passive"))
      (node (ref "R82") (pin "1") (pinfunction "1_1") (pintype "passive"))
      (node (ref "R84") (pin "1") (pinfunction "1_1") (pintype "passive"))
      (node (ref "R85") (pin "1") (pinfunction "1_1") (pintype "passive"))
      (node (ref "R86") (pin "1") (pinfunction "1_1") (pintype "passive"))
      (node (ref "R88") (pin "1") (pinfunction "1_1") (pintype "passive"))
      (node (ref "R89") (pin "1") (pinfunction "1_1") (pintype "passive"))
      (node (ref "U4") (pin "2") (pintype "passive"))
      (node (ref "U4") (pin "4") (pintype "passive"))
      (node (ref "U4") (pin "6") (pintype "passive"))
      (node (ref "U4") (pin "8") (pintype "passive"))
      (node (ref "VD4") (pin "2") (pinfunction "A_2") (pintype "passive"))
      (node (ref "VD5") (pin "2") (pinfunction "A_2") (pintype "passive"))
      (node (ref "VD6") (pin "2") (pinfunction "A_2") (pintype "passive"))
      (node (ref "VD7") (pin "2") (pinfunction "A_2") (pintype "passive"))
      (node (ref "XP9") (pin "16") (pintype "passive"))
      (node (ref "XP9") (pin "20") (pintype "passive"))
      (node (ref "XP9") (pin "7") (pintype "passive"))
    )
    (net (code "45") (name "Net-(DA14-IN+)") (class "Default")
      (node (ref "DA14") (pin "3") (pinfunction "IN+_3") (pintype "passive"))
      (node (ref "R55") (pin "2") (pinfunction "2_2") (pintype "passive"))
      (node (ref "R59") (pin "1") (pinfunction "1_1") (pintype "passive"))
    )
    (net (code "46") (name "Net-(DA14-IN-)") (class "Default")
      (node (ref "C79") (pin "2") (pinfunction "2_2") (pintype "passive"))
      (node (ref "DA14") (pin "4") (pinfunction "IN-_4") (pintype "passive"))
      (node (ref "R71") (pin "1") (pinfunction "1_1") (pintype "passive"))
      (node (ref "U5") (pin "4") (pintype "passive"))
    )
    (net (code "47") (name "Net-(DA14-OUT)") (class "Default")
      (node (ref "C79") (pin "1") (pinfunction "1_1") (pintype "passive"))
      (node (ref "DA14") (pin "1") (pinfunction "OUT_1") (pintype "passive"))
      (node (ref "R69") (pin "1") (pinfunction "1_1") (pintype "passive"))
    )
    (net (code "48") (name "Net-(DA15-IN+)") (class "Default")
      (node (ref "DA15") (pin "3") (pinfunction "IN+_3") (pintype "passive"))
      (node (ref "R75") (pin "1") (pinfunction "1_1") (pintype "passive"))
      (node (ref "U5") (pin "5") (pintype "passive"))
    )
    (net (code "49") (name "Net-(DA15-IN-)") (class "Default")
      (node (ref "DA15") (pin "1") (pinfunction "OUT_1") (pintype "passive"))
      (node (ref "DA15") (pin "4") (pinfunction "IN-_4") (pintype "passive"))
      (node (ref "R76") (pin "1") (pinfunction "1_1") (pintype "passive"))
    )
    (net (code "50") (name "Net-(DA18-IN+)") (class "Default")
      (node (ref "C92") (pin "1") (pinfunction "1_1") (pintype "passive"))
      (node (ref "DA18") (pin "3") (pinfunction "IN+_3") (pintype "passive"))
      (node (ref "R81") (pin "2") (pinfunction "2_2") (pintype "passive"))
    )
    (net (code "51") (name "Net-(DA18-IN-)") (class "Default")
      (node (ref "DA18") (pin "4") (pinfunction "IN-_4") (pintype "passive"))
      (node (ref "R83") (pin "2") (pinfunction "2_2") (pintype "passive"))
      (node (ref "R87") (pin "1") (pinfunction "1_1") (pintype "passive"))
    )
    (net (code "52") (name "Net-(DD10-C1+)") (class "Default")
      (node (ref "C78") (pin "1") (pinfunction "1_1") (pintype "passive"))
      (node (ref "DD10") (pin "9") (pinfunction "C1+_9") (pintype "passive"))
    )
    (net (code "53") (name "Net-(DD10-C1-)") (class "Default")
      (node (ref "C78") (pin "2") (pinfunction "2_2") (pintype "passive"))
      (node (ref "DD10") (pin "2") (pinfunction "C1-_2") (pintype "passive"))
    )
    (net (code "54") (name "Net-(DD10-ROUT)") (class "Default")
      (node (ref "DD10") (pin "5") (pinfunction "ROUT_5") (pintype "passive"))
      (node (ref "DD11") (pin "7") (pinfunction "VIA_7") (pintype "passive"))
    )
    (net (code "55") (name "Net-(DD10-TIN)") (class "Default")
      (node (ref "DD10") (pin "4") (pinfunction "TIN_4") (pintype "passive"))
      (node (ref "DD11") (pin "6") (pinfunction "VOB_6") (pintype "passive"))
    )
    (net (code "56") (name "Net-(DD10-V-)") (class "Default")
      (node (ref "C76") (pin "1") (pinfunction "1_1") (pintype "passive"))
      (node (ref "DD10") (pin "3") (pinfunction "V-_3") (pintype "passive"))
    )
    (net (code "57") (name "Net-(DD12-VIA)") (class "Default")
      (node (ref "DD12") (pin "3") (pinfunction "VIA_3") (pintype "passive"))
      (node (ref "R67") (pin "2") (pinfunction "2_2") (pintype "passive"))
      (node (ref "VD7") (pin "1") (pinfunction "K_1") (pintype "passive"))
    )
    (net (code "58") (name "Net-(DD12-VIB)") (class "Default")
      (node (ref "DD12") (pin "4") (pinfunction "VIB_4") (pintype "passive"))
      (node (ref "R61") (pin "2") (pinfunction "2_2") (pintype "passive"))
      (node (ref "VD6") (pin "1") (pinfunction "K_1") (pintype "passive"))
    )
    (net (code "59") (name "Net-(DD12-VIC)") (class "Default")
      (node (ref "DD12") (pin "5") (pinfunction "VIC_5") (pintype "passive"))
      (node (ref "R68") (pin "2") (pinfunction "2_2") (pintype "passive"))
      (node (ref "VD5") (pin "1") (pinfunction "K_1") (pintype "passive"))
    )
    (net (code "60") (name "Net-(DD12-VID)") (class "Default")
      (node (ref "DD12") (pin "6") (pinfunction "VID_6") (pintype "passive"))
      (node (ref "R62") (pin "2") (pinfunction "2_2") (pintype "passive"))
      (node (ref "VD4") (pin "1") (pinfunction "K_1") (pintype "passive"))
    )
    (net (code "61") (name "Net-(DD13-VO)") (class "Default")
      (node (ref "DD13") (pin "6") (pinfunction "VO_6") (pintype "passive"))
      (node (ref "R81") (pin "1") (pinfunction "1_1") (pintype "passive"))
    )
    (net (code "62") (name "Net-(R63-Pad2)") (class "Default")
      (node (ref "R63") (pin "2") (pinfunction "2_2") (pintype "passive"))
      (node (ref "U4") (pin "1") (pintype "passive"))
    )
    (net (code "63") (name "Net-(R64-Pad2)") (class "Default")
      (node (ref "R64") (pin "2") (pinfunction "2_2") (pintype "passive"))
      (node (ref "U4") (pin "3") (pintype "passive"))
    )
    (net (code "64") (name "Net-(R65-Pad2)") (class "Default")
      (node (ref "R65") (pin "2") (pinfunction "2_2") (pintype "passive"))
      (node (ref "U4") (pin "5") (pintype "passive"))
    )
    (net (code "65") (name "Net-(R66-Pad2)") (class "Default")
      (node (ref "R66") (pin "2") (pinfunction "2_2") (pintype "passive"))
      (node (ref "U4") (pin "7") (pintype "passive"))
    )
    (net (code "66") (name "Net-(R69-Pad2)") (class "Default")
      (node (ref "R69") (pin "2") (pinfunction "2_2") (pintype "passive"))
      (node (ref "U5") (pin "2") (pintype "passive"))
    )
    (net (code "67") (name "Net-(R77-Pad1)") (class "Default")
      (node (ref "R77") (pin "1") (pinfunction "1_1") (pintype "passive"))
      (node (ref "U6") (pin "1") (pintype "passive"))
    )
    (net (code "68") (name "Net-(R78-Pad1)") (class "Default")
      (node (ref "R78") (pin "1") (pinfunction "1_1") (pintype "passive"))
      (node (ref "U6") (pin "3") (pintype "passive"))
    )
    (net (code "69") (name "Net-(R79-Pad1)") (class "Default")
      (node (ref "R79") (pin "1") (pinfunction "1_1") (pintype "passive"))
      (node (ref "U6") (pin "5") (pintype "passive"))
    )
    (net (code "70") (name "Net-(R80-Pad1)") (class "Default")
      (node (ref "R80") (pin "1") (pinfunction "1_1") (pintype "passive"))
      (node (ref "U6") (pin "7") (pintype "passive"))
    )
    (net (code "71") (name "unconnected-(DA16-NC-Pad5)") (class "Default")
      (node (ref "DA16") (pin "5") (pinfunction "NC_5") (pintype "passive"))
    )
    (net (code "72") (name "unconnected-(DA16-NC-Pad8)") (class "Default")
      (node (ref "DA16") (pin "8") (pinfunction "NC_8") (pintype "passive"))
    )
    (net (code "73") (name "unconnected-(DA16-ON{slash}OFF-Pad3)") (class "Default")
      (node (ref "DA16") (pin "3") (pinfunction "ON/OFF_3") (pintype "passive"))
    )
    (net (code "74") (name "unconnected-(DD12-NC-Pad7)") (class "Default")
      (node (ref "DD12") (pin "7") (pinfunction "NC_7") (pintype "passive"))
    )
    (net (code "75") (name "unconnected-(U5-Pad7)") (class "Default")
      (node (ref "U5") (pin "7") (pintype "passive"))
    )
    (net (code "76") (name "unconnected-(U5-Pad8)") (class "Default")
      (node (ref "U5") (pin "8") (pintype "passive"))
    )
  )
)
